# 4_-RF.net
KiCad netlist of a schematic drawn in Altium Designer
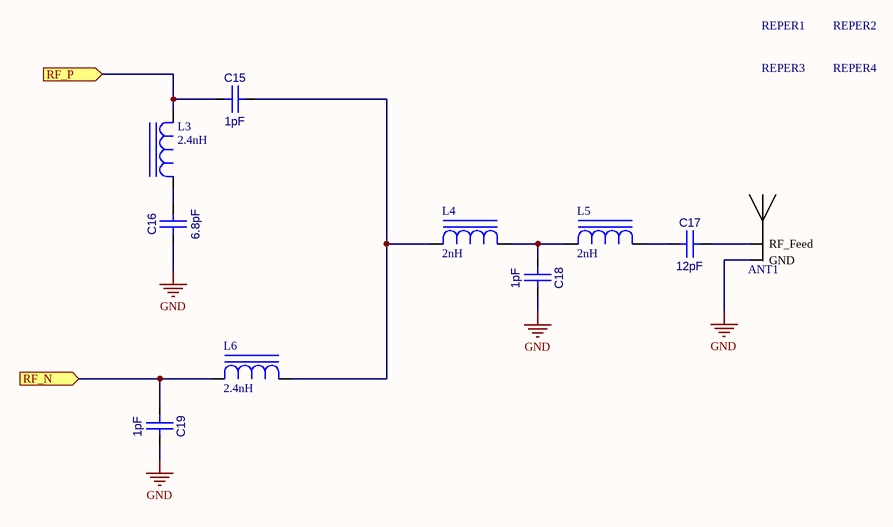
[diagram p0: [4]-RF.SchDoc]

(export (version "E")
  (design (tool "Eeschema 10.0.6"))
  (components
    (comp (ref "ANT1")
      (value "IFA_TI_2.4G_Reference")
      (footprint "ANT_IFA_2.4G_BEST")
      (libsource (lib "gprs_modem_2") (part "ANT_WiFi_IFA_BEST"))
    )
    (comp (ref "C15")
      (value "1pF")
      (footprint "CC0603")
      (description "CC0603")
      (libsource (lib "gprs_modem_2") (part "CC0603"))
    )
    (comp (ref "C16")
      (value "6.8pF")
      (footprint "CC0603")
      (description "CC0603")
      (libsource (lib "gprs_modem_2") (part "CC0603"))
    )
    (comp (ref "C17")
      (value "12pF")
      (footprint "CC0603")
      (description "CC0603")
      (libsource (lib "gprs_modem_2") (part "CC0603"))
    )
    (comp (ref "C18")
      (value "1pF")
      (footprint "CC0603")
      (description "CC0603")
      (libsource (lib "gprs_modem_2") (part "CC0603"))
    )
    (comp (ref "C19")
      (value "1pF")
      (footprint "CC0603")
      (description "CC0603")
      (libsource (lib "gprs_modem_2") (part "CC0603"))
    )
    (comp (ref "L3")
      (value "2.4nH")
      (footprint "L0402")
      (description "L0402")
      (libsource (lib "gprs_modem_2") (part "L0402"))
    )
    (comp (ref "L4")
      (value "2nH")
      (footprint "L0402")
      (description "L0402")
      (libsource (lib "gprs_modem_2") (part "L0402"))
    )
    (comp (ref "L5")
      (value "2nH")
      (footprint "L0402")
      (description "L0402")
      (libsource (lib "gprs_modem_2") (part "L0402"))
    )
    (comp (ref "L6")
      (value "2.4nH")
      (footprint "L0402")
      (description "L0402")
      (libsource (lib "gprs_modem_2") (part "L0402"))
    )
    (comp (ref "REPER1")
      (value "REPER1.2")
      (footprint "REPER1.2")
      (libsource (lib "gprs_modem_2") (part "REPER1.2"))
    )
    (comp (ref "REPER2")
      (value "REPER1.2")
      (footprint "REPER1.2")
      (libsource (lib "gprs_modem_2") (part "REPER1.2"))
    )
    (comp (ref "REPER3")
      (value "REPER1.2")
      (footprint "REPER1.2")
      (libsource (lib "gprs_modem_2") (part "REPER1.2"))
    )
    (comp (ref "REPER4")
      (value "REPER1.2")
      (footprint "REPER1.2")
      (libsource (lib "gprs_modem_2") (part "REPER1.2"))
    )
  )
  (nets
    (net (code "1") (name "/RF_N") (class "Default")
      (node (ref "C19") (pin "1") (pinfunction "A_1") (pintype "passive"))
      (node (ref "L6") (pin "1") (pinfunction "A_1") (pintype "passive"))
    )
    (net (code "2") (name "/RF_P") (class "Default")
      (node (ref "C15") (pin "1") (pinfunction "A_1") (pintype "passive"))
      (node (ref "L3") (pin "2") (pinfunction "C_2") (pintype "passive"))
    )
    (net (code "3") (name "GND") (class "Default")
      (node (ref "ANT1") (pin "2") (pinfunction "GND_2") (pintype "passive"))
      (node (ref "C16") (pin "1") (pinfunction "A_1") (pintype "passive"))
      (node (ref "C18") (pin "2") (pinfunction "B_2") (pintype "passive"))
      (node (ref "C19") (pin "2") (pinfunction "B_2") (pintype "passive"))
    )
    (net (code "4") (name "Net-(ANT1-RF_Feed)") (class "Default")
      (node (ref "ANT1") (pin "1") (pinfunction "RF_Feed_1") (pintype "passive"))
      (node (ref "C17") (pin "2") (pinfunction "B_2") (pintype "passive"))
    )
    (net (code "5") (name "Net-(C15-B)") (class "Default")
      (node (ref "C15") (pin "2") (pinfunction "B_2") (pintype "passive"))
      (node (ref "L4") (pin "1") (pinfunction "A_1") (pintype "passive"))
      (node (ref "L6") (pin "2") (pinfunction "C_2") (pintype "passive"))
    )
    (net (code "6") (name "Net-(C16-B)") (class "Default")
      (node (ref "C16") (pin "2") (pinfunction "B_2") (pintype "passive"))
      (node (ref "L3") (pin "1") (pinfunction "A_1") (pintype "passive"))
    )
    (net (code "7") (name "Net-(C17-A)") (class "Default")
      (node (ref "C17") (pin "1") (pinfunction "A_1") (pintype "passive"))
      (node (ref "L5") (pin "2") (pinfunction "C_2") (pintype "passive"))
    )
    (net (code "8") (name "Net-(C18-A)") (class "Default")
      (node (ref "C18") (pin "1") (pinfunction "A_1") (pintype "passive"))
      (node (ref "L4") (pin "2") (pinfunction "C_2") (pintype "passive"))
      (node (ref "L5") (pin "1") (pinfunction "A_1") (pintype "passive"))
    )
    (net (code "9") (name "unconnected-(REPER1-Pad1)") (class "Default")
      (node (ref "REPER1") (pin "1") (pintype "passive"))
    )
    (net (code "10") (name "unconnected-(REPER2-Pad1)") (class "Default")
      (node (ref "REPER2") (pin "1") (pintype "passive"))
    )
    (net (code "11") (name "unconnected-(REPER3-Pad1)") (class "Default")
      (node (ref "REPER3") (pin "1") (pintype "passive"))
    )
    (net (code "12") (name "unconnected-(REPER4-Pad1)") (class "Default")
      (node (ref "REPER4") (pin "1") (pintype "passive"))
    )
  )
)
